# RatDBS-Plastic2032Battery-WithRegulator.net
KiCad netlist of a schematic drawn in EAGLE
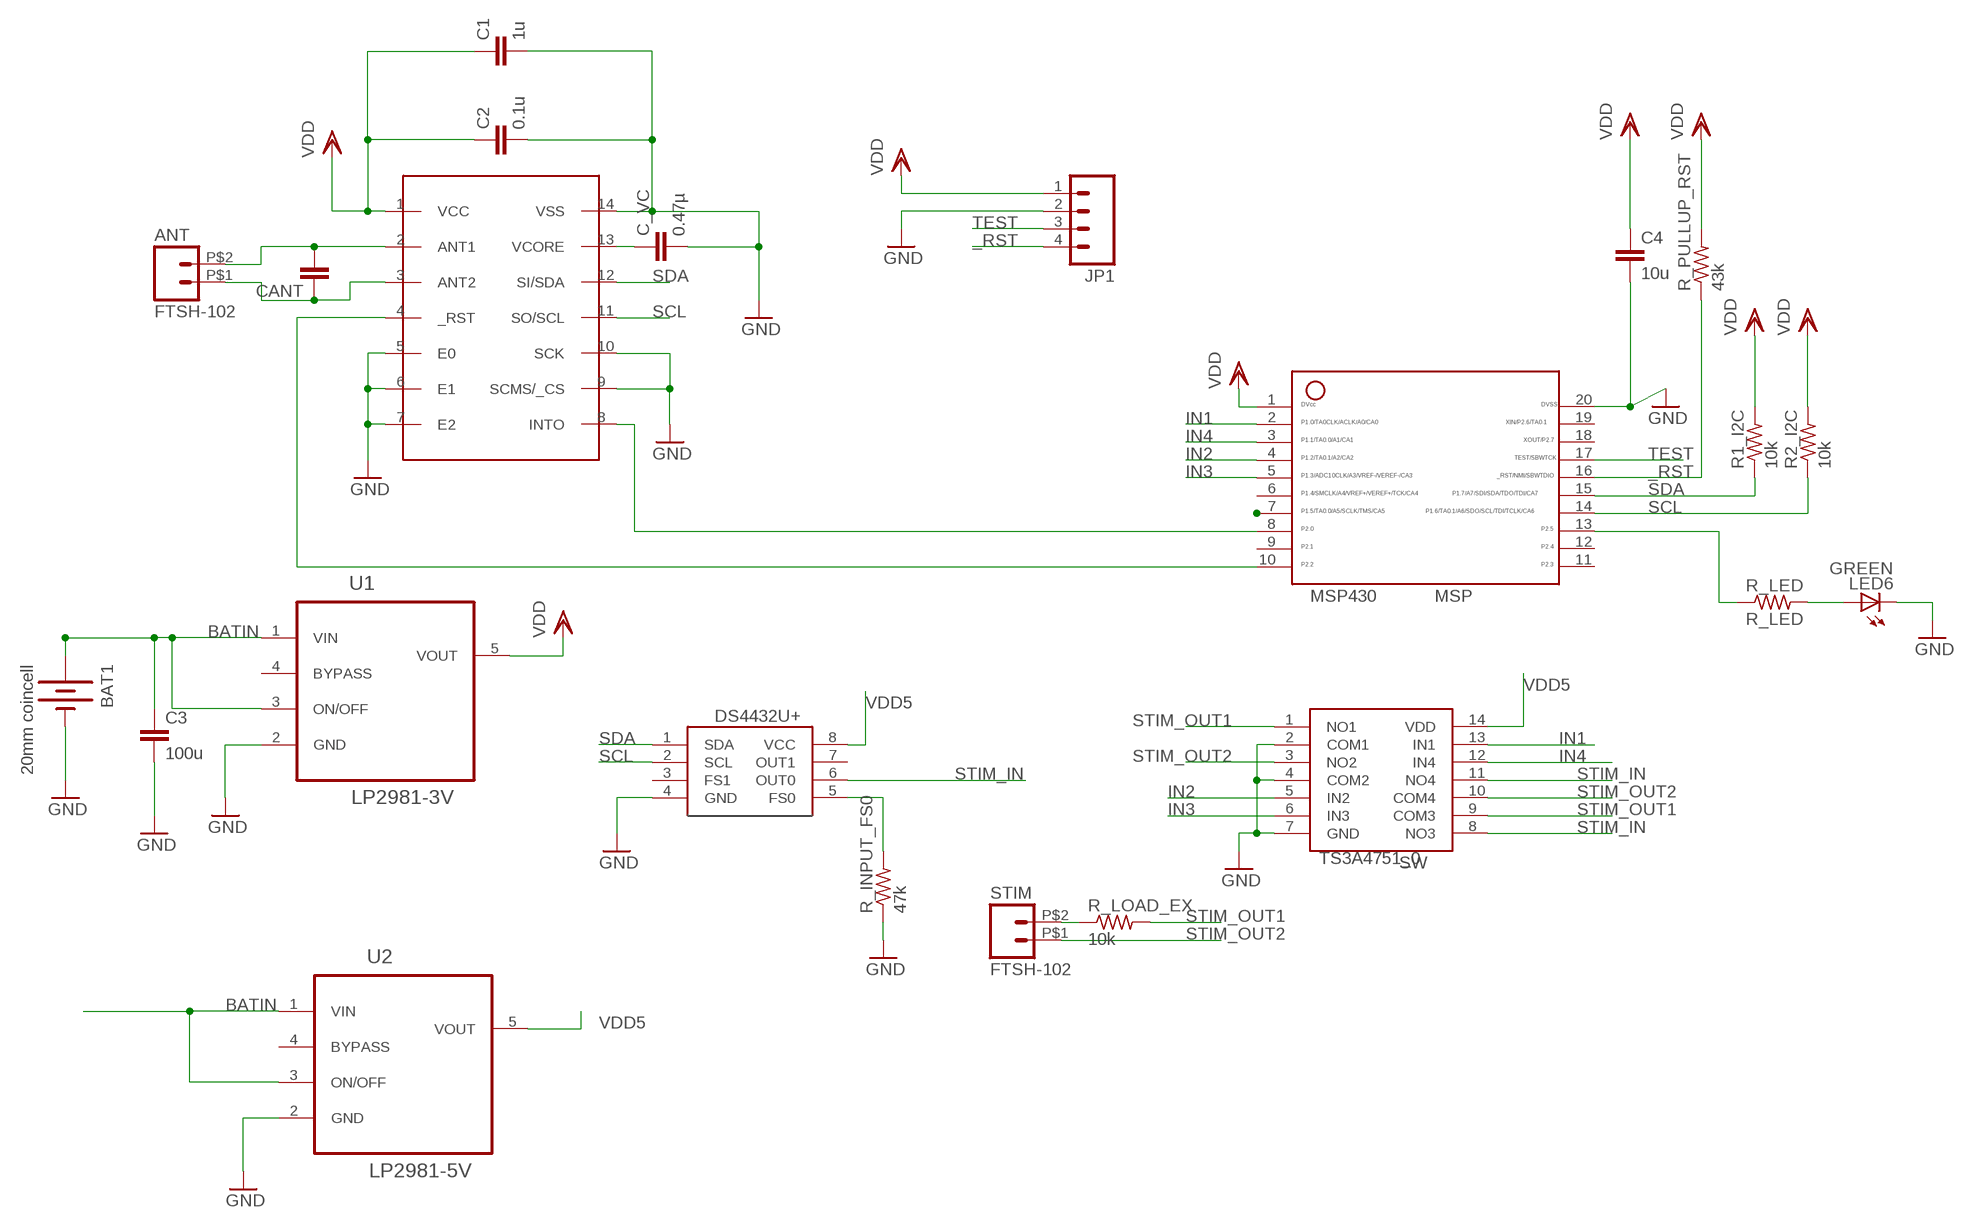
[diagram p0: schematic, sheet 1]

(export (version "E")
  (design (tool "Eeschema 10.0.6"))
  (components
    (comp (ref "ANT")
      (value "FTSH-102")
      (footprint "eagle-import:FTSH-102-DH")
      (libsource (lib "eagle-import") (part "FTSH-102"))
    )
    (comp (ref "BAT1")
      (value "20mm coincell")
      (footprint "eagle-import:BATTCOM_20MM_PLASTIC_STUDS")
      (libsource (lib "eagle-import") (part "BATTERY"))
    )
    (comp (ref "C1")
      (value "1u")
      (footprint "eagle-import:C0603")
      (libsource (lib "eagle-import") (part "C-EUC0603"))
    )
    (comp (ref "C2")
      (value "0.1u")
      (footprint "eagle-import:C0603")
      (libsource (lib "eagle-import") (part "C-EUC0603"))
    )
    (comp (ref "C3")
      (value "100u")
      (footprint "eagle-import:C1206")
      (libsource (lib "eagle-import") (part "C-EUC1206"))
    )
    (comp (ref "C4")
      (value "10u")
      (footprint "eagle-import:C1206")
      (libsource (lib "eagle-import") (part "C-EUC1206"))
    )
    (comp (ref "CANT")
      (value "C-EUC0603")
      (footprint "eagle-import:C0603")
      (libsource (lib "eagle-import") (part "C-EUC0603"))
    )
    (comp (ref "C_VC")
      (value "0.47µ")
      (footprint "eagle-import:C0603")
      (libsource (lib "eagle-import") (part "C-EUC0603"))
    )
    (comp (ref "DS4432U+")
      (value "DS4432U+")
      (footprint "eagle-import:8_PIN")
      (libsource (lib "eagle-import") (part "DS4432U+"))
    )
    (comp (ref "JP1")
      (value "M041.27MM")
      (footprint "eagle-import:1X04-1.27MM")
      (libsource (lib "eagle-import") (part "M041.27MM"))
    )
    (comp (ref "LED6")
      (value "GREEN")
      (footprint "eagle-import:LED-1206")
      (libsource (lib "eagle-import") (part "LED1206"))
    )
    (comp (ref "MSP430")
      (value "MSP")
      (footprint "eagle-import:20_PIN")
      (libsource (lib "eagle-import") (part "MSP430"))
    )
    (comp (ref "R1_I2C")
      (value "10k")
      (footprint "eagle-import:R0603")
      (libsource (lib "eagle-import") (part "R-US_R0603"))
    )
    (comp (ref "R2_I2C")
      (value "10k")
      (footprint "eagle-import:R0603")
      (libsource (lib "eagle-import") (part "R-US_R0603"))
    )
    (comp (ref "R_INPUT_FS0")
      (value "47k")
      (footprint "eagle-import:R0603")
      (libsource (lib "eagle-import") (part "R-US_R0603"))
    )
    (comp (ref "R_LED")
      (value "R_LED")
      (footprint "eagle-import:R0603")
      (libsource (lib "eagle-import") (part "R-US_R0603"))
    )
    (comp (ref "R_LOAD_EX")
      (value "10k")
      (footprint "eagle-import:R0603")
      (libsource (lib "eagle-import") (part "R-US_R0603"))
    )
    (comp (ref "R_PULLUP_RST")
      (value "43k")
      (footprint "eagle-import:R0603")
      (libsource (lib "eagle-import") (part "R-US_R0603"))
    )
    (comp (ref "STIM")
      (value "FTSH-102")
      (footprint "eagle-import:FTSH-102-DH")
      (libsource (lib "eagle-import") (part "FTSH-102"))
    )
    (comp (ref "TS3A4751_0")
      (value "SW")
      (footprint "eagle-import:14_PIN")
      (libsource (lib "eagle-import") (part "TS3A4751"))
    )
    (comp (ref "U$1")
      (value "RF")
      (footprint "eagle-import:PW_R-PDSO-G14")
      (libsource (lib "eagle-import") (part "RF430CL330H"))
    )
    (comp (ref "U1")
      (value "LP2981-3V")
      (footprint "eagle-import:SOT95P280X145-5N")
      (fields (field (name "MPN") "LP2985A-33DBVTE4"))
      (libsource (lib "eagle-import") (part "LP2985A-33DBVTE4"))
    )
    (comp (ref "U2")
      (value "LP2981-5V")
      (footprint "eagle-import:SOT95P280X145-5N")
      (fields (field (name "MPN") "LP2985A-33DBVTE4"))
      (libsource (lib "eagle-import") (part "LP2985A-33DBVTE4"))
    )
  )
  (nets
    (net (code "1") (name "/BATIN") (class "Default")
      (node (ref "BAT1") (pin "1") (pinfunction "+_1") (pintype "power_in"))
      (node (ref "C3") (pin "1") (pinfunction "1_1") (pintype "passive"))
      (node (ref "U1") (pin "1") (pinfunction "VIN_1") (pintype "power_in"))
      (node (ref "U1") (pin "3") (pinfunction "ON/OFF_3") (pintype "input"))
      (node (ref "U2") (pin "1") (pinfunction "VIN_1") (pintype "power_in"))
      (node (ref "U2") (pin "3") (pinfunction "ON/OFF_3") (pintype "input"))
    )
    (net (code "2") (name "/IN1") (class "Default")
      (node (ref "MSP430") (pin "2") (pinfunction "2_2") (pintype "bidirectional"))
      (node (ref "TS3A4751_0") (pin "13") (pinfunction "IN1_13") (pintype "bidirectional"))
    )
    (net (code "3") (name "/IN2") (class "Default")
      (node (ref "MSP430") (pin "4") (pinfunction "4_4") (pintype "bidirectional"))
      (node (ref "TS3A4751_0") (pin "5") (pinfunction "IN2_5") (pintype "bidirectional"))
    )
    (net (code "4") (name "/IN3") (class "Default")
      (node (ref "MSP430") (pin "5") (pinfunction "5_5") (pintype "bidirectional"))
      (node (ref "TS3A4751_0") (pin "6") (pinfunction "IN3_6") (pintype "bidirectional"))
    )
    (net (code "5") (name "/IN4") (class "Default")
      (node (ref "MSP430") (pin "3") (pinfunction "3_3") (pintype "bidirectional"))
      (node (ref "TS3A4751_0") (pin "12") (pinfunction "IN4_12") (pintype "bidirectional"))
    )
    (net (code "6") (name "/SCL") (class "Default")
      (node (ref "DS4432U+") (pin "2") (pinfunction "SCL_2") (pintype "bidirectional"))
      (node (ref "MSP430") (pin "14") (pinfunction "14_14") (pintype "bidirectional"))
      (node (ref "R2_I2C") (pin "1") (pinfunction "1_1") (pintype "passive"))
      (node (ref "U$1") (pin "11") (pinfunction "SO/SCL_11") (pintype "bidirectional"))
    )
    (net (code "7") (name "/SDA") (class "Default")
      (node (ref "DS4432U+") (pin "1") (pinfunction "SDA_1") (pintype "bidirectional"))
      (node (ref "MSP430") (pin "15") (pinfunction "15_15") (pintype "bidirectional"))
      (node (ref "R1_I2C") (pin "1") (pinfunction "1_1") (pintype "passive"))
      (node (ref "U$1") (pin "12") (pinfunction "SI/SDA_12") (pintype "bidirectional"))
    )
    (net (code "8") (name "/STIM_IN") (class "Default")
      (node (ref "DS4432U+") (pin "6") (pinfunction "OUT0_6") (pintype "bidirectional"))
      (node (ref "TS3A4751_0") (pin "11") (pinfunction "NO4_11") (pintype "bidirectional"))
      (node (ref "TS3A4751_0") (pin "8") (pinfunction "NO3_8") (pintype "bidirectional"))
    )
    (net (code "9") (name "/STIM_OUT1") (class "Default")
      (node (ref "R_LOAD_EX") (pin "2") (pinfunction "2_2") (pintype "passive"))
      (node (ref "TS3A4751_0") (pin "1") (pinfunction "NO1_1") (pintype "bidirectional"))
      (node (ref "TS3A4751_0") (pin "9") (pinfunction "COM3_9") (pintype "bidirectional"))
    )
    (net (code "10") (name "/STIM_OUT2") (class "Default")
      (node (ref "STIM") (pin "P$1") (pinfunction "1_P$1") (pintype "passive"))
      (node (ref "TS3A4751_0") (pin "10") (pinfunction "COM4_10") (pintype "bidirectional"))
      (node (ref "TS3A4751_0") (pin "3") (pinfunction "NO2_3") (pintype "bidirectional"))
    )
    (net (code "11") (name "/TEST") (class "Default")
      (node (ref "JP1") (pin "3") (pinfunction "3_3") (pintype "passive"))
      (node (ref "MSP430") (pin "17") (pinfunction "17_17") (pintype "bidirectional"))
    )
    (net (code "12") (name "/VDD5") (class "Default")
      (node (ref "DS4432U+") (pin "8") (pinfunction "VCC_8") (pintype "power_in"))
      (node (ref "TS3A4751_0") (pin "14") (pinfunction "VDD_14") (pintype "bidirectional"))
      (node (ref "U2") (pin "5") (pinfunction "VOUT_5") (pintype "output"))
    )
    (net (code "13") (name "/_RST") (class "Default")
      (node (ref "JP1") (pin "4") (pinfunction "4_4") (pintype "passive"))
      (node (ref "MSP430") (pin "16") (pinfunction "16_16") (pintype "bidirectional"))
      (node (ref "R_PULLUP_RST") (pin "1") (pinfunction "1_1") (pintype "passive"))
    )
    (net (code "14") (name "GND") (class "Default")
      (node (ref "BAT1") (pin "2") (pinfunction "-_2") (pintype "power_in"))
      (node (ref "C1") (pin "2") (pinfunction "2_2") (pintype "passive"))
      (node (ref "C2") (pin "2") (pinfunction "2_2") (pintype "passive"))
      (node (ref "C3") (pin "2") (pinfunction "2_2") (pintype "passive"))
      (node (ref "C4") (pin "2") (pinfunction "2_2") (pintype "passive"))
      (node (ref "C_VC") (pin "2") (pinfunction "2_2") (pintype "passive"))
      (node (ref "DS4432U+") (pin "4") (pinfunction "GND_4") (pintype "power_in"))
      (node (ref "JP1") (pin "2") (pinfunction "2_2") (pintype "passive"))
      (node (ref "LED6") (pin "C") (pinfunction "C_C") (pintype "passive"))
      (node (ref "MSP430") (pin "20") (pinfunction "20_20") (pintype "bidirectional"))
      (node (ref "R_INPUT_FS0") (pin "1") (pinfunction "1_1") (pintype "passive"))
      (node (ref "TS3A4751_0") (pin "2") (pinfunction "COM1_2") (pintype "bidirectional"))
      (node (ref "TS3A4751_0") (pin "4") (pinfunction "COM2_4") (pintype "bidirectional"))
      (node (ref "TS3A4751_0") (pin "7") (pinfunction "GND_7") (pintype "bidirectional"))
      (node (ref "U$1") (pin "10") (pinfunction "SCK_10") (pintype "bidirectional"))
      (node (ref "U$1") (pin "14") (pinfunction "VSS_14") (pintype "power_in"))
      (node (ref "U$1") (pin "5") (pinfunction "E0_5") (pintype "bidirectional"))
      (node (ref "U$1") (pin "6") (pinfunction "E1_6") (pintype "bidirectional"))
      (node (ref "U$1") (pin "7") (pinfunction "E2_7") (pintype "bidirectional"))
      (node (ref "U$1") (pin "9") (pinfunction "SCMS/_CS_9") (pintype "bidirectional"))
      (node (ref "U1") (pin "2") (pinfunction "GND_2") (pintype "passive"))
      (node (ref "U2") (pin "2") (pinfunction "GND_2") (pintype "passive"))
    )
    (net (code "15") (name "Net-(ANT-1)") (class "Default")
      (node (ref "ANT") (pin "P$1") (pinfunction "1_P$1") (pintype "passive"))
      (node (ref "CANT") (pin "1") (pinfunction "1_1") (pintype "passive"))
      (node (ref "U$1") (pin "3") (pinfunction "ANT2_3") (pintype "bidirectional"))
    )
    (net (code "16") (name "Net-(ANT-2)") (class "Default")
      (node (ref "ANT") (pin "P$2") (pinfunction "2_P$2") (pintype "passive"))
      (node (ref "CANT") (pin "2") (pinfunction "2_2") (pintype "passive"))
      (node (ref "U$1") (pin "2") (pinfunction "ANT1_2") (pintype "bidirectional"))
    )
    (net (code "17") (name "Net-(DS4432U+-FS0)") (class "Default")
      (node (ref "DS4432U+") (pin "5") (pinfunction "FS0_5") (pintype "bidirectional"))
      (node (ref "R_INPUT_FS0") (pin "2") (pinfunction "2_2") (pintype "passive"))
    )
    (net (code "18") (name "Net-(LED6-PadA)") (class "Default")
      (node (ref "LED6") (pin "A") (pinfunction "A_A") (pintype "passive"))
      (node (ref "R_LED") (pin "2") (pinfunction "2_2") (pintype "passive"))
    )
    (net (code "19") (name "Net-(MSP430-Pad13)") (class "Default")
      (node (ref "MSP430") (pin "13") (pinfunction "13_13") (pintype "bidirectional"))
      (node (ref "R_LED") (pin "1") (pinfunction "1_1") (pintype "passive"))
    )
    (net (code "20") (name "Net-(STIM-2)") (class "Default")
      (node (ref "R_LOAD_EX") (pin "1") (pinfunction "1_1") (pintype "passive"))
      (node (ref "STIM") (pin "P$2") (pinfunction "2_P$2") (pintype "passive"))
    )
    (net (code "21") (name "Net-(U$1-INTO)") (class "Default")
      (node (ref "MSP430") (pin "8") (pinfunction "8_8") (pintype "bidirectional"))
      (node (ref "U$1") (pin "8") (pinfunction "INTO_8") (pintype "bidirectional"))
    )
    (net (code "22") (name "Net-(U$1-VCORE)") (class "Default")
      (node (ref "C_VC") (pin "1") (pinfunction "1_1") (pintype "passive"))
      (node (ref "U$1") (pin "13") (pinfunction "VCORE_13") (pintype "bidirectional"))
    )
    (net (code "23") (name "Net-(U$1-_RST)") (class "Default")
      (node (ref "MSP430") (pin "10") (pinfunction "10_10") (pintype "bidirectional"))
      (node (ref "U$1") (pin "4") (pinfunction "_RST_4") (pintype "bidirectional"))
    )
    (net (code "24") (name "VDD") (class "Default")
      (node (ref "C1") (pin "1") (pinfunction "1_1") (pintype "passive"))
      (node (ref "C2") (pin "1") (pinfunction "1_1") (pintype "passive"))
      (node (ref "C4") (pin "1") (pinfunction "1_1") (pintype "passive"))
      (node (ref "JP1") (pin "1") (pinfunction "1_1") (pintype "passive"))
      (node (ref "MSP430") (pin "1") (pinfunction "1_1") (pintype "bidirectional"))
      (node (ref "R1_I2C") (pin "2") (pinfunction "2_2") (pintype "passive"))
      (node (ref "R2_I2C") (pin "2") (pinfunction "2_2") (pintype "passive"))
      (node (ref "R_PULLUP_RST") (pin "2") (pinfunction "2_2") (pintype "passive"))
      (node (ref "U$1") (pin "1") (pinfunction "VCC_1") (pintype "power_in"))
      (node (ref "U1") (pin "5") (pinfunction "VOUT_5") (pintype "output"))
    )
    (net (code "25") (name "unconnected-(DS4432U+-FS1-Pad3)") (class "Default")
      (node (ref "DS4432U+") (pin "3") (pinfunction "FS1_3") (pintype "bidirectional"))
    )
    (net (code "26") (name "unconnected-(DS4432U+-OUT1-Pad7)") (class "Default")
      (node (ref "DS4432U+") (pin "7") (pinfunction "OUT1_7") (pintype "bidirectional"))
    )
    (net (code "27") (name "unconnected-(MSP430-Pad6)") (class "Default")
      (node (ref "MSP430") (pin "6") (pinfunction "6_6") (pintype "bidirectional"))
    )
    (net (code "28") (name "unconnected-(MSP430-Pad7)") (class "Default")
      (node (ref "MSP430") (pin "7") (pinfunction "7_7") (pintype "bidirectional"))
    )
    (net (code "29") (name "unconnected-(MSP430-Pad9)") (class "Default")
      (node (ref "MSP430") (pin "9") (pinfunction "9_9") (pintype "bidirectional"))
    )
    (net (code "30") (name "unconnected-(MSP430-Pad11)") (class "Default")
      (node (ref "MSP430") (pin "11") (pinfunction "11_11") (pintype "bidirectional"))
    )
    (net (code "31") (name "unconnected-(MSP430-Pad12)") (class "Default")
      (node (ref "MSP430") (pin "12") (pinfunction "12_12") (pintype "bidirectional"))
    )
    (net (code "32") (name "unconnected-(MSP430-Pad18)") (class "Default")
      (node (ref "MSP430") (pin "18") (pinfunction "18_18") (pintype "bidirectional"))
    )
    (net (code "33") (name "unconnected-(MSP430-Pad19)") (class "Default")
      (node (ref "MSP430") (pin "19") (pinfunction "19_19") (pintype "bidirectional"))
    )
    (net (code "34") (name "unconnected-(U1-BYPASS-Pad4)") (class "Default")
      (node (ref "U1") (pin "4") (pinfunction "BYPASS_4") (pintype "input"))
    )
    (net (code "35") (name "unconnected-(U2-BYPASS-Pad4)") (class "Default")
      (node (ref "U2") (pin "4") (pinfunction "BYPASS_4") (pintype "input"))
    )
  )
)
